# SGP40_Breakout.net
KiCad netlist of a schematic drawn in EAGLE
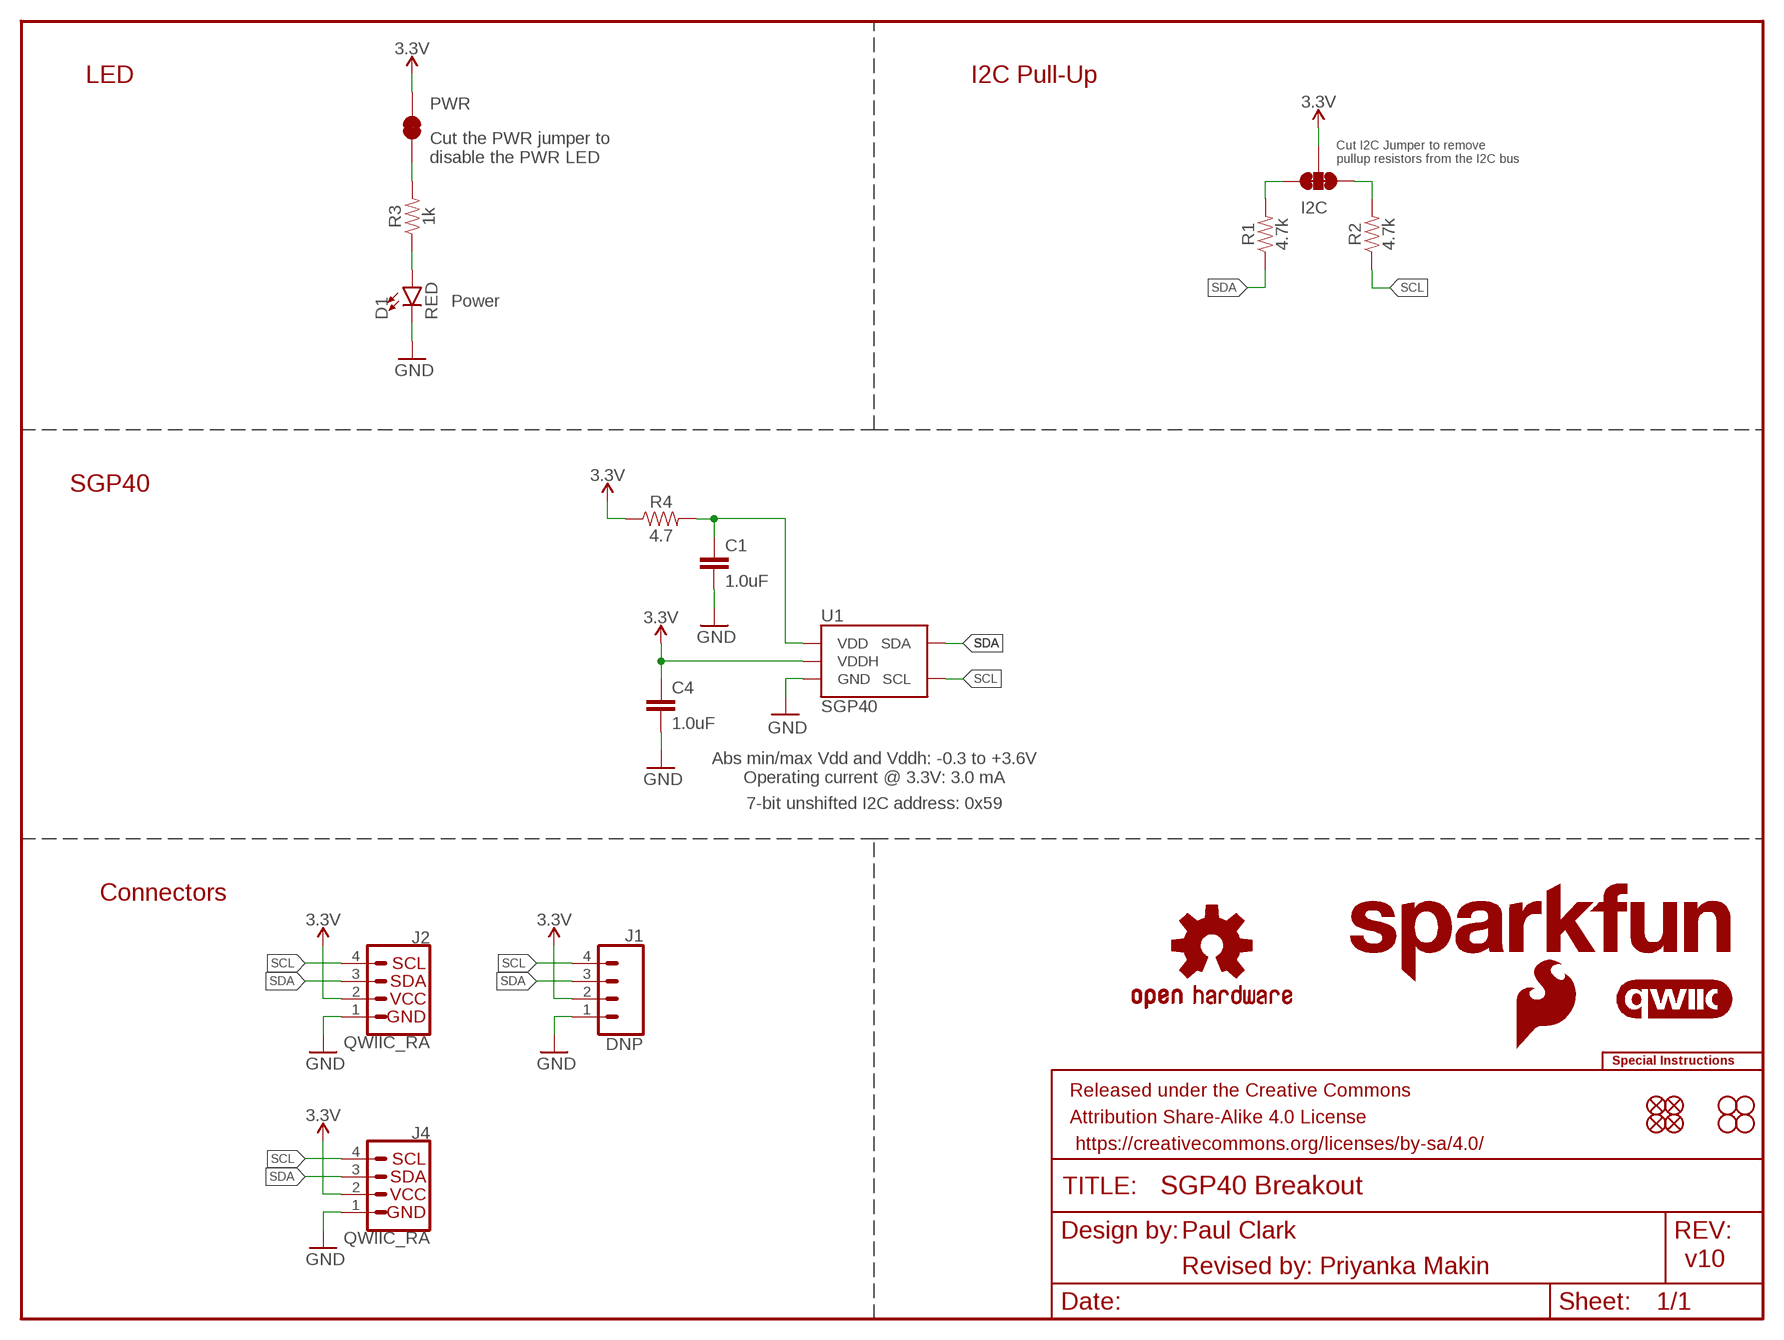
[diagram p0: schematic, sheet 1]

(export (version "E")
  (design (tool "Eeschema 10.0.6"))
  (components
    (comp (ref "C1")
      (value "1.0uF")
      (footprint "eagle-import:0603")
      (libsource (lib "eagle-import") (part "1.0UF-0603-16V-10%-X7R"))
    )
    (comp (ref "C4")
      (value "1.0uF")
      (footprint "eagle-import:0603")
      (libsource (lib "eagle-import") (part "1.0UF-0603-16V-10%-X7R"))
    )
    (comp (ref "D1")
      (value "RED")
      (footprint "eagle-import:LED-0603")
      (libsource (lib "eagle-import") (part "LED-RED0603"))
    )
    (comp (ref "FRAME1")
      (value "FRAME-LETTER")
      (footprint "eagle-import:CREATIVE_COMMONS")
      (libsource (lib "eagle-import") (part "FRAME-LETTER"))
    )
    (comp (ref "I2C")
      (value "JUMPER-SMT_3_2-NC_TRACE_SILK")
      (footprint "eagle-import:SMT-JUMPER_3_2-NC_TRACE_SILK")
      (libsource (lib "eagle-import") (part "JUMPER-SMT_3_2-NC_TRACE_SILK"))
    )
    (comp (ref "J1")
      (value "DNP")
      (footprint "eagle-import:1X04_NO_SILK")
      (libsource (lib "eagle-import") (part "CONN_041X04_NO_SILK"))
    )
    (comp (ref "J2")
      (value "QWIIC_RA")
      (footprint "eagle-import:JST04_1MM_RA")
      (libsource (lib "eagle-import") (part "QWIIC_CONNECTORJS-1MM"))
    )
    (comp (ref "J4")
      (value "QWIIC_RA")
      (footprint "eagle-import:JST04_1MM_RA")
      (libsource (lib "eagle-import") (part "QWIIC_CONNECTORJS-1MM"))
    )
    (comp (ref "JP1")
      (value "FIDUCIAL0.2MM")
      (footprint "eagle-import:FIDUCIAL-0.2MM")
      (libsource (lib "eagle-import") (part "FIDUCIAL0.2MM"))
    )
    (comp (ref "JP2")
      (value "FIDUCIAL0.2MM")
      (footprint "eagle-import:FIDUCIAL-0.2MM")
      (libsource (lib "eagle-import") (part "FIDUCIAL0.2MM"))
    )
    (comp (ref "JP3")
      (value "STAND-OFF")
      (footprint "eagle-import:STAND-OFF")
      (libsource (lib "eagle-import") (part "STAND-OFF"))
    )
    (comp (ref "JP4")
      (value "STAND-OFF")
      (footprint "eagle-import:STAND-OFF")
      (libsource (lib "eagle-import") (part "STAND-OFF"))
    )
    (comp (ref "JP5")
      (value "FIDUCIAL0.2MM")
      (footprint "eagle-import:FIDUCIAL-0.2MM")
      (libsource (lib "eagle-import") (part "FIDUCIAL0.2MM"))
    )
    (comp (ref "JP6")
      (value "FIDUCIAL0.2MM")
      (footprint "eagle-import:FIDUCIAL-0.2MM")
      (libsource (lib "eagle-import") (part "FIDUCIAL0.2MM"))
    )
    (comp (ref "JP7")
      (value "STAND-OFF")
      (footprint "eagle-import:STAND-OFF")
      (libsource (lib "eagle-import") (part "STAND-OFF"))
    )
    (comp (ref "JP8")
      (value "STAND-OFF")
      (footprint "eagle-import:STAND-OFF")
      (libsource (lib "eagle-import") (part "STAND-OFF"))
    )
    (comp (ref "LOGO1")
      (value "SPECIAL_INSTRUCTIONS-ORDERING")
      (footprint "eagle-import:ORDERING_INSTRUCTIONS")
      (libsource (lib "eagle-import") (part "SPECIAL_INSTRUCTIONS-ORDERING"))
    )
    (comp (ref "LOGO2")
      (value "QWIIC_LOGO_5MM")
      (footprint "eagle-import:QWIIC_5MM")
      (libsource (lib "eagle-import") (part "QWIIC_LOGO_5MM"))
    )
    (comp (ref "LOGO3")
      (value "SFE_LOGO_NAME.1_INCH")
      (footprint "eagle-import:SFE_LOGO_NAME_.1")
      (libsource (lib "eagle-import") (part "SFE_LOGO_NAME.1_INCH"))
    )
    (comp (ref "LOGO4")
      (value "SFE_LOGO_FLAME.1_INCH")
      (footprint "eagle-import:SFE_LOGO_FLAME_.1")
      (libsource (lib "eagle-import") (part "SFE_LOGO_FLAME.1_INCH"))
    )
    (comp (ref "LOGO5")
      (value "OSHW-LOGOS")
      (footprint "eagle-import:OSHW-LOGO-S")
      (libsource (lib "eagle-import") (part "OSHW-LOGOS"))
    )
    (comp (ref "LOGO6")
      (value "SFE_LOGO_NAME.1_INCH")
      (footprint "eagle-import:SFE_LOGO_NAME_.1")
      (libsource (lib "eagle-import") (part "SFE_LOGO_NAME.1_INCH"))
    )
    (comp (ref "PWR")
      (value "JUMPER-SMT_2_NC_TRACE_SILK")
      (footprint "eagle-import:SMT-JUMPER_2_NC_TRACE_SILK")
      (libsource (lib "eagle-import") (part "JUMPER-SMT_2_NC_TRACE_SILK"))
    )
    (comp (ref "R1")
      (value "4.7k")
      (footprint "eagle-import:0603")
      (libsource (lib "eagle-import") (part "4.7KOHM-0603-1/10W-1%"))
    )
    (comp (ref "R2")
      (value "4.7k")
      (footprint "eagle-import:0603")
      (libsource (lib "eagle-import") (part "4.7KOHM-0603-1/10W-1%"))
    )
    (comp (ref "R3")
      (value "1k")
      (footprint "eagle-import:0603")
      (libsource (lib "eagle-import") (part "1KOHM-0603-1/10W-1%"))
    )
    (comp (ref "R4")
      (value "4.7")
      (footprint "eagle-import:0603")
      (libsource (lib "eagle-import") (part "4.7OHM-0603-1/10W-1%"))
    )
    (comp (ref "U1")
      (value "SGP40")
      (footprint "eagle-import:SGP40")
      (fields (field (name "DIGIKEY_PART") "1649-SGP40-D-R4CT-ND"))
      (libsource (lib "eagle-import") (part "SGP40"))
    )
  )
  (nets
    (net (code "1") (name "3.3V") (class "Default")
      (node (ref "C4") (pin "1") (pinfunction "1_1") (pintype "passive"))
      (node (ref "I2C") (pin "2") (pinfunction "2_2") (pintype "passive"))
      (node (ref "J1") (pin "2") (pinfunction "2_2") (pintype "passive"))
      (node (ref "J2") (pin "2") (pinfunction "2_2") (pintype "power_in"))
      (node (ref "J4") (pin "2") (pinfunction "2_2") (pintype "power_in"))
      (node (ref "PWR") (pin "2") (pinfunction "2_2") (pintype "passive"))
      (node (ref "R4") (pin "1") (pinfunction "1_1") (pintype "passive"))
      (node (ref "U1") (pin "5") (pinfunction "VDDH_5") (pintype "power_in"))
    )
    (net (code "2") (name "GND") (class "Default")
      (node (ref "C1") (pin "2") (pinfunction "2_2") (pintype "passive"))
      (node (ref "C4") (pin "2") (pinfunction "2_2") (pintype "passive"))
      (node (ref "D1") (pin "C") (pinfunction "C_C") (pintype "passive"))
      (node (ref "J1") (pin "1") (pinfunction "1_1") (pintype "passive"))
      (node (ref "J2") (pin "1") (pinfunction "1_1") (pintype "power_in"))
      (node (ref "J4") (pin "1") (pinfunction "1_1") (pintype "power_in"))
      (node (ref "U1") (pin "2") (pinfunction "GND_2") (pintype "power_in"))
      (node (ref "U1") (pin "4") (pinfunction "GND_4") (pintype "power_in"))
      (node (ref "U1") (pin "DIEPAD") (pinfunction "GND_DIEPAD") (pintype "power_in"))
    )
    (net (code "3") (name "Net-(D1-PadA)") (class "Default")
      (node (ref "D1") (pin "A") (pinfunction "A_A") (pintype "passive"))
      (node (ref "R3") (pin "1") (pinfunction "1_1") (pintype "passive"))
    )
    (net (code "4") (name "Net-(I2C-Pad1)") (class "Default")
      (node (ref "I2C") (pin "1") (pinfunction "1_1") (pintype "passive"))
      (node (ref "R2") (pin "2") (pinfunction "2_2") (pintype "passive"))
    )
    (net (code "5") (name "Net-(I2C-Pad3)") (class "Default")
      (node (ref "I2C") (pin "3") (pinfunction "3_3") (pintype "passive"))
      (node (ref "R1") (pin "2") (pinfunction "2_2") (pintype "passive"))
    )
    (net (code "6") (name "Net-(PWR-Pad1)") (class "Default")
      (node (ref "PWR") (pin "1") (pinfunction "1_1") (pintype "passive"))
      (node (ref "R3") (pin "2") (pinfunction "2_2") (pintype "passive"))
    )
    (net (code "7") (name "Net-(U1-VDD)") (class "Default")
      (node (ref "C1") (pin "1") (pinfunction "1_1") (pintype "passive"))
      (node (ref "R4") (pin "2") (pinfunction "2_2") (pintype "passive"))
      (node (ref "U1") (pin "1") (pinfunction "VDD_1") (pintype "power_in"))
    )
    (net (code "8") (name "SCL") (class "Default")
      (node (ref "J1") (pin "4") (pinfunction "4_4") (pintype "passive"))
      (node (ref "J2") (pin "4") (pinfunction "4_4") (pintype "passive"))
      (node (ref "J4") (pin "4") (pinfunction "4_4") (pintype "passive"))
      (node (ref "R2") (pin "1") (pinfunction "1_1") (pintype "passive"))
      (node (ref "U1") (pin "6") (pinfunction "SCL_6") (pintype "bidirectional"))
    )
    (net (code "9") (name "SDA") (class "Default")
      (node (ref "J1") (pin "3") (pinfunction "3_3") (pintype "passive"))
      (node (ref "J2") (pin "3") (pinfunction "3_3") (pintype "passive"))
      (node (ref "J4") (pin "3") (pinfunction "3_3") (pintype "passive"))
      (node (ref "R1") (pin "1") (pinfunction "1_1") (pintype "passive"))
      (node (ref "U1") (pin "3") (pinfunction "SDA_3") (pintype "bidirectional"))
    )
  )
)
